# MICROCONTROLLER.net
KiCad netlist of a schematic drawn in Altium Designer
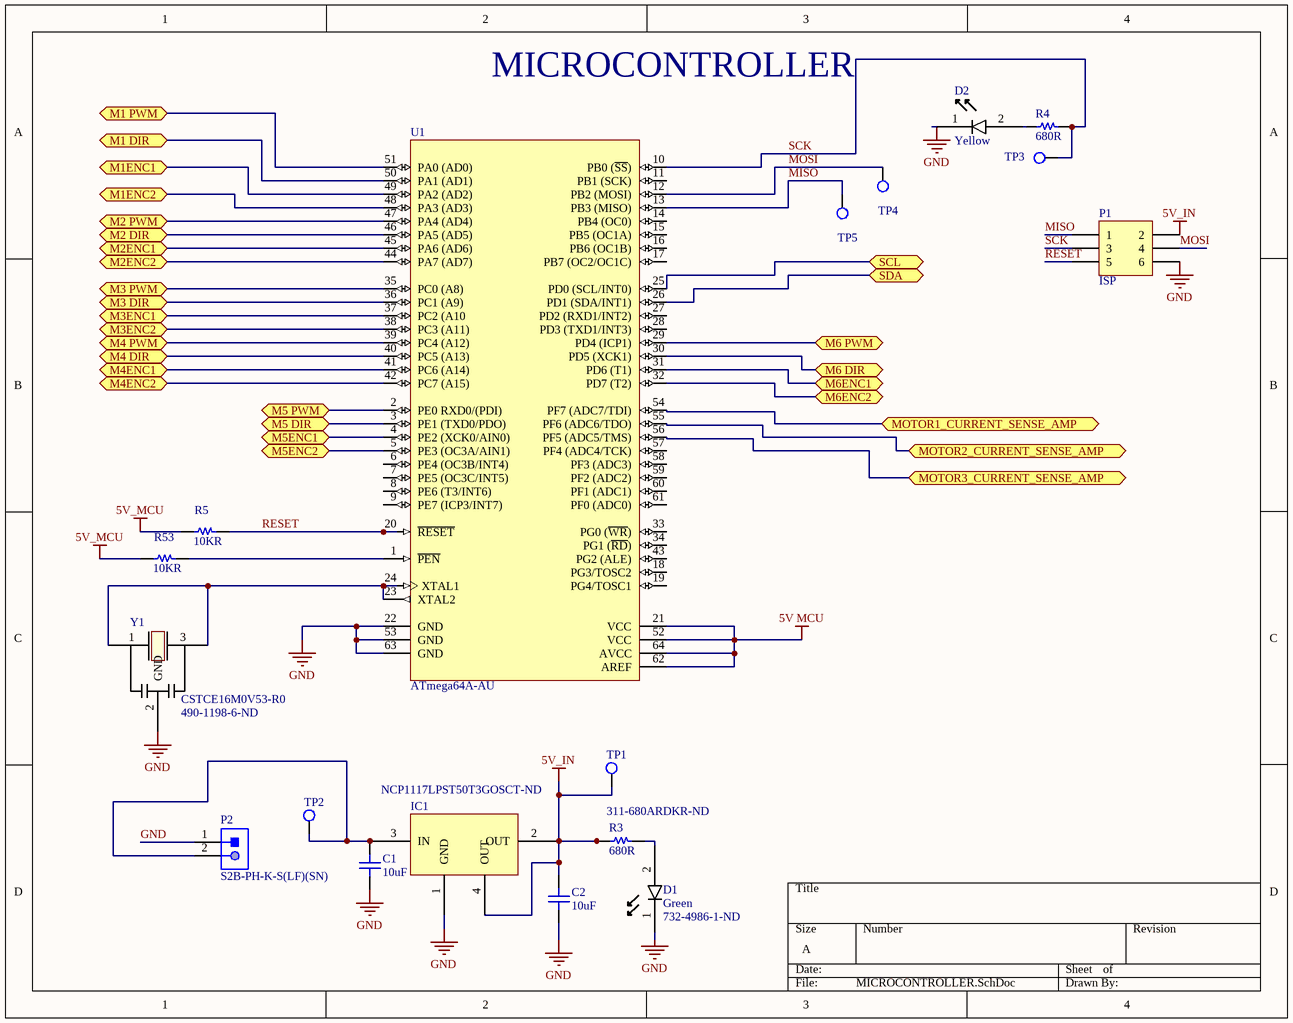
[diagram p0: MICROCONTROLLER.SchDoc]

(export (version "E")
  (design (tool "Eeschema 10.0.6"))
  (components
    (comp (ref "C1")
      (value "10uF")
      (footprint "CAP_ADJ_0805")
      (description "CERAMIC CAPACITOR SMD 0805")
      (fields
        (field (name "MANUFACTURER") "Taiyo Yuden")
        (field (name "MANUFACTURER PART NUMBER") "TMK212BBJ106KG-T")
      )
      (libsource (lib "ORI_MANIPULATOR_BRD") (part "CAP_ADJ_0805"))
    )
    (comp (ref "C2")
      (value "10uF")
      (footprint "CAP_ADJ_0805")
      (description "CERAMIC CAPACITOR SMD 0805")
      (fields
        (field (name "MANUFACTURER") "Taiyo Yuden")
        (field (name "MANUFACTURER PART NUMBER") "TMK212BBJ106KG-T")
      )
      (libsource (lib "ORI_MANIPULATOR_BRD") (part "CAP_ADJ_0805"))
    )
    (comp (ref "D1")
      (value "Green")
      (footprint "LED_150080VS75000")
      (description "LED GREEN CLEAR 0805 SMD")
      (fields
        (field (name "MANUFACTURER") "Wurth Electronics")
        (field (name "MANUFACTURER PART NUMBER") "150080VS75000")
        (field (name "SUPPLIER PART NUMBER 1") "732-4986-1-ND")
      )
      (libsource (lib "ORI_MANIPULATOR_BRD") (part "LED_GRN_150080VS75000"))
    )
    (comp (ref "D2")
      (value "Yellow")
      (footprint "LED_150080VS75000")
      (description "LED YELLOW CLEAR 0805 SMD")
      (fields
        (field (name "MANUFACTURER") "Wurth Electronics")
        (field (name "MANUFACTURER PART NUMBER") "150080YS75000")
      )
      (libsource (lib "ORI_MANIPULATOR_BRD") (part "LED_YLW_150080YS75000"))
    )
    (comp (ref "IC1")
      (value "NCP1117LPST50T3GOSCT-ND")
      (footprint "NCP1117LPST50T3GOSCT-ND")
      (description "IC REG LINEAR 5V 1A SOT223-4")
      (fields
        (field (name "MANUFACTURER") "ON Semiconductor")
        (field (name "MANUFACTURER PART NUMBER") "NCP1117LPST50T3G")
      )
      (libsource (lib "ORI_MANIPULATOR_BRD") (part "NCP1117LPST50T3GOSCT-ND"))
    )
    (comp (ref "P1")
      (value "ISP")
      (footprint "HDR2X3")
      (description "Header, 3-Pin, Dual row")
      (fields (field (name "PUBLISHER") "Altium Limited"))
      (libsource (lib "Miscellaneous Connectors") (part "Header 3X2"))
    )
    (comp (ref "P2")
      (value "S2B-PH-K-S(LF)(SN)")
      (footprint "JST-S2B-PH-K-S_V")
      (fields (field (name "TOLERANCE") "20%"))
      (libsource (lib "Altium Content Vault") (part "CN-1P-M-R2"))
    )
    (comp (ref "R3")
      (value "680R")
      (footprint "RES_ADJ_0805_YAGEO")
      (description "RESISTOR 0805 YAGEO")
      (fields
        (field (name "SUPPLIER PART NUMBER 1") "311-680ARDKR-ND")
        (field (name "MANUFACTURER") "Yageo")
        (field (name "MANUFACTURER PART NUMBER") "RC0805JR-07680RL")
      )
      (libsource (lib "ORI_MANIPULATOR_BRD") (part "RES_ADJ_0805"))
    )
    (comp (ref "R4")
      (value "680R")
      (footprint "RES_ADJ_0805_YAGEO")
      (description "RESISTOR 0805 YAGEO")
      (fields
        (field (name "MANUFACTURER") "Yageo")
        (field (name "MANUFACTURER PART NUMBER") "RC0805JR-07680RL")
      )
      (libsource (lib "ORI_MANIPULATOR_BRD") (part "RES_ADJ_0805"))
    )
    (comp (ref "R5")
      (value "10KR")
      (footprint "RES_ADJ_0805_YAGEO")
      (description "RESISTOR 0805 YAGEO")
      (fields
        (field (name "MANUFACTURER") "Yageo")
        (field (name "MANUFACTURER PART NUMBER") "RC0805JR-0710KL")
      )
      (libsource (lib "ORI_MANIPULATOR_BRD") (part "RES_ADJ_0805"))
    )
    (comp (ref "R53")
      (value "10KR")
      (footprint "RES_ADJ_0805_YAGEO")
      (description "RESISTOR 0805 YAGEO")
      (fields
        (field (name "MANUFACTURER") "Yageo")
        (field (name "MANUFACTURER PART NUMBER") "RC0805JR-0710KL")
      )
      (libsource (lib "ORI_MANIPULATOR_BRD") (part "RES_ADJ_0805"))
    )
    (comp (ref "TP1")
      (value "TEST_POINT")
      (footprint "TEST_POINT")
      (description "TEST POINT PAD")
      (libsource (lib "ORI_MANIPULATOR_BRD") (part "TEST_POINT"))
    )
    (comp (ref "TP2")
      (value "TEST_POINT")
      (footprint "TEST_POINT")
      (description "TEST POINT PAD")
      (libsource (lib "ORI_MANIPULATOR_BRD") (part "TEST_POINT"))
    )
    (comp (ref "TP3")
      (value "TEST_POINT")
      (footprint "TEST_POINT")
      (description "TEST POINT PAD")
      (libsource (lib "ORI_MANIPULATOR_BRD") (part "TEST_POINT"))
    )
    (comp (ref "TP4")
      (value "TEST_POINT")
      (footprint "TEST_POINT")
      (description "TEST POINT PAD")
      (libsource (lib "ORI_MANIPULATOR_BRD") (part "TEST_POINT"))
    )
    (comp (ref "TP5")
      (value "TEST_POINT")
      (footprint "TEST_POINT")
      (description "TEST POINT PAD")
      (libsource (lib "ORI_MANIPULATOR_BRD") (part "TEST_POINT"))
    )
    (comp (ref "U1")
      (value "ATmega64A-AU")
      (footprint "64A_M")
      (libsource (lib "Altium Content Vault") (part "MC-8B-ATM64A-SQ64"))
    )
    (comp (ref "Y1")
      (value "CSTCE16M0V53-R0")
      (footprint "CSTCE16M0V53-R0")
      (description "CER RES 16.0000MHZ 15PF SMD")
      (fields
        (field (name "MANUFACTURER") "Murata")
        (field (name "TOLERANCE") "0.5%")
        (field (name "SUPPLIER PART NUMBER 1") "490-1198-6-ND")
      )
      (libsource (lib "ORI_MANIPULATOR_BRD") (part "CSTCE16M0V53-R0"))
    )
  )
  (nets
    (net (code "1") (name "/M1 DIR") (class "Default")
      (node (ref "U1") (pin "50") (pinfunction "PA1_(AD1)_50") (pintype "bidirectional"))
    )
    (net (code "2") (name "/M1 PWM") (class "Default")
      (node (ref "U1") (pin "51") (pinfunction "PA0_(AD0)_51") (pintype "bidirectional"))
    )
    (net (code "3") (name "/M1ENC1") (class "Default")
      (node (ref "U1") (pin "49") (pinfunction "PA2_(AD2)_49") (pintype "bidirectional"))
    )
    (net (code "4") (name "/M1ENC2") (class "Default")
      (node (ref "U1") (pin "48") (pinfunction "PA3_(AD3)_48") (pintype "bidirectional"))
    )
    (net (code "5") (name "/M2 DIR") (class "Default")
      (node (ref "U1") (pin "46") (pinfunction "PA5_(AD5)_46") (pintype "bidirectional"))
    )
    (net (code "6") (name "/M2 PWM") (class "Default")
      (node (ref "U1") (pin "47") (pinfunction "PA4_(AD4)_47") (pintype "bidirectional"))
    )
    (net (code "7") (name "/M2ENC1") (class "Default")
      (node (ref "U1") (pin "45") (pinfunction "PA6_(AD6)_45") (pintype "bidirectional"))
    )
    (net (code "8") (name "/M2ENC2") (class "Default")
      (node (ref "U1") (pin "44") (pinfunction "PA7_(AD7)_44") (pintype "bidirectional"))
    )
    (net (code "9") (name "/M3 DIR") (class "Default")
      (node (ref "U1") (pin "36") (pinfunction "PC1_(A9)_36") (pintype "bidirectional"))
    )
    (net (code "10") (name "/M3 PWM") (class "Default")
      (node (ref "U1") (pin "35") (pinfunction "PC0_(A8)_35") (pintype "bidirectional"))
    )
    (net (code "11") (name "/M3ENC1") (class "Default")
      (node (ref "U1") (pin "37") (pinfunction "PC2_(A10_37") (pintype "bidirectional"))
    )
    (net (code "12") (name "/M3ENC2") (class "Default")
      (node (ref "U1") (pin "38") (pinfunction "PC3_(A11)_38") (pintype "bidirectional"))
    )
    (net (code "13") (name "/M4 DIR") (class "Default")
      (node (ref "U1") (pin "40") (pinfunction "PC5_(A13)_40") (pintype "bidirectional"))
    )
    (net (code "14") (name "/M4 PWM") (class "Default")
      (node (ref "U1") (pin "39") (pinfunction "PC4_(A12)_39") (pintype "bidirectional"))
    )
    (net (code "15") (name "/M4ENC1") (class "Default")
      (node (ref "U1") (pin "41") (pinfunction "PC6_(A14)_41") (pintype "bidirectional"))
    )
    (net (code "16") (name "/M4ENC2") (class "Default")
      (node (ref "U1") (pin "42") (pinfunction "PC7_(A15)_42") (pintype "bidirectional"))
    )
    (net (code "17") (name "/M5 DIR") (class "Default")
      (node (ref "U1") (pin "3") (pinfunction "PE1_(TXD0/PDO)_3") (pintype "bidirectional"))
    )
    (net (code "18") (name "/M5 PWM") (class "Default")
      (node (ref "U1") (pin "2") (pinfunction "PE0_RXD0/(PDI)_2") (pintype "bidirectional"))
    )
    (net (code "19") (name "/M5ENC1") (class "Default")
      (node (ref "U1") (pin "4") (pinfunction "PE2_(XCK0/AIN0)_4") (pintype "bidirectional"))
    )
    (net (code "20") (name "/M5ENC2") (class "Default")
      (node (ref "U1") (pin "5") (pinfunction "PE3_(OC3A/AIN1)_5") (pintype "bidirectional"))
    )
    (net (code "21") (name "/M6 DIR") (class "Default")
      (node (ref "U1") (pin "30") (pinfunction "PD5_(XCK1)_30") (pintype "bidirectional"))
    )
    (net (code "22") (name "/M6 PWM") (class "Default")
      (node (ref "U1") (pin "29") (pinfunction "PD4_(ICP1)_29") (pintype "bidirectional"))
    )
    (net (code "23") (name "/M6ENC1") (class "Default")
      (node (ref "U1") (pin "31") (pinfunction "PD6_(T1)_31") (pintype "bidirectional"))
    )
    (net (code "24") (name "/M6ENC2") (class "Default")
      (node (ref "U1") (pin "32") (pinfunction "PD7_(T2)_32") (pintype "bidirectional"))
    )
    (net (code "25") (name "/MISO") (class "Default")
      (node (ref "P1") (pin "1") (pinfunction "1_1") (pintype "passive"))
      (node (ref "TP5") (pin "1") (pinfunction "1_1") (pintype "passive"))
      (node (ref "U1") (pin "13") (pinfunction "PB3_(MISO)_13") (pintype "bidirectional"))
    )
    (net (code "26") (name "/MOSI") (class "Default")
      (node (ref "P1") (pin "4") (pinfunction "4_4") (pintype "passive"))
      (node (ref "TP4") (pin "1") (pinfunction "1_1") (pintype "passive"))
      (node (ref "U1") (pin "12") (pinfunction "PB2_(MOSI)_12") (pintype "bidirectional"))
    )
    (net (code "27") (name "/MOTOR1_CURRENT_SENSE_AMP") (class "Default")
      (node (ref "U1") (pin "54") (pinfunction "PF7_(ADC7/TDI)_54") (pintype "bidirectional"))
    )
    (net (code "28") (name "/MOTOR2_CURRENT_SENSE_AMP") (class "Default")
      (node (ref "U1") (pin "55") (pinfunction "PF6_(ADC6/TDO)_55") (pintype "bidirectional"))
    )
    (net (code "29") (name "/MOTOR3_CURRENT_SENSE_AMP") (class "Default")
      (node (ref "U1") (pin "56") (pinfunction "PF5_(ADC5/TMS)_56") (pintype "bidirectional"))
    )
    (net (code "30") (name "/RESET") (class "Default")
      (node (ref "P1") (pin "5") (pinfunction "5_5") (pintype "passive"))
      (node (ref "R5") (pin "2") (pinfunction "2_2") (pintype "passive"))
      (node (ref "U1") (pin "20") (pinfunction "~{RESET}_20") (pintype "input"))
    )
    (net (code "31") (name "/SCK") (class "Default")
      (node (ref "P1") (pin "3") (pinfunction "3_3") (pintype "passive"))
      (node (ref "R4") (pin "2") (pinfunction "2_2") (pintype "passive"))
      (node (ref "TP3") (pin "1") (pinfunction "1_1") (pintype "passive"))
      (node (ref "U1") (pin "10") (pinfunction "PB0_(~{SS})_10") (pintype "bidirectional"))
    )
    (net (code "32") (name "/SCL") (class "Default")
      (node (ref "U1") (pin "25") (pinfunction "PD0_(SCL/INT0)_25") (pintype "bidirectional"))
    )
    (net (code "33") (name "/SDA") (class "Default")
      (node (ref "U1") (pin "26") (pinfunction "PD1_(SDA/INT1)_26") (pintype "bidirectional"))
    )
    (net (code "34") (name "5V MCU") (class "Default")
      (node (ref "U1") (pin "21") (pinfunction "VCC_21") (pintype "power_in"))
      (node (ref "U1") (pin "52") (pinfunction "VCC_52") (pintype "power_in"))
      (node (ref "U1") (pin "62") (pinfunction "AREF_62") (pintype "power_in"))
      (node (ref "U1") (pin "64") (pinfunction "AVCC_64") (pintype "power_in"))
    )
    (net (code "35") (name "5V_IN") (class "Default")
      (node (ref "C2") (pin "2") (pinfunction "2_2") (pintype "passive"))
      (node (ref "IC1") (pin "2") (pinfunction "OUT_2") (pintype "passive"))
      (node (ref "IC1") (pin "4") (pinfunction "OUT_4") (pintype "passive"))
      (node (ref "P1") (pin "2") (pinfunction "2_2") (pintype "passive"))
      (node (ref "R3") (pin "1") (pinfunction "1_1") (pintype "passive"))
      (node (ref "TP1") (pin "1") (pinfunction "1_1") (pintype "passive"))
    )
    (net (code "36") (name "5V_MCU") (class "Default")
      (node (ref "R5") (pin "1") (pinfunction "1_1") (pintype "passive"))
      (node (ref "R53") (pin "1") (pinfunction "1_1") (pintype "passive"))
    )
    (net (code "37") (name "GND") (class "Default")
      (node (ref "C1") (pin "1") (pinfunction "1_1") (pintype "passive"))
      (node (ref "C2") (pin "1") (pinfunction "1_1") (pintype "passive"))
      (node (ref "D1") (pin "1") (pinfunction "1_1") (pintype "passive"))
      (node (ref "D2") (pin "1") (pinfunction "1_1") (pintype "passive"))
      (node (ref "IC1") (pin "1") (pinfunction "GND_1") (pintype "passive"))
      (node (ref "P1") (pin "6") (pinfunction "6_6") (pintype "passive"))
      (node (ref "P2") (pin "1") (pinfunction "1_1") (pintype "passive"))
      (node (ref "U1") (pin "22") (pinfunction "GND_22") (pintype "power_in"))
      (node (ref "U1") (pin "53") (pinfunction "GND_53") (pintype "power_in"))
      (node (ref "U1") (pin "63") (pinfunction "GND_63") (pintype "power_in"))
      (node (ref "Y1") (pin "2") (pinfunction "GND_2") (pintype "passive"))
    )
    (net (code "38") (name "Net-(D1-Pad2)") (class "Default")
      (node (ref "D1") (pin "2") (pinfunction "2_2") (pintype "passive"))
      (node (ref "R3") (pin "2") (pinfunction "2_2") (pintype "passive"))
    )
    (net (code "39") (name "Net-(D2-Pad2)") (class "Default")
      (node (ref "D2") (pin "2") (pinfunction "2_2") (pintype "passive"))
      (node (ref "R4") (pin "1") (pinfunction "1_1") (pintype "passive"))
    )
    (net (code "40") (name "Net-(IC1-IN)") (class "Default")
      (node (ref "C1") (pin "2") (pinfunction "2_2") (pintype "passive"))
      (node (ref "IC1") (pin "3") (pinfunction "IN_3") (pintype "passive"))
      (node (ref "P2") (pin "2") (pinfunction "2_2") (pintype "passive"))
      (node (ref "TP2") (pin "1") (pinfunction "1_1") (pintype "passive"))
    )
    (net (code "41") (name "Net-(U1-XTAL1)") (class "Default")
      (node (ref "U1") (pin "23") (pinfunction "XTAL2_23") (pintype "output"))
      (node (ref "U1") (pin "24") (pinfunction "XTAL1_24") (pintype "input"))
      (node (ref "Y1") (pin "1") (pinfunction "1_1") (pintype "passive"))
      (node (ref "Y1") (pin "3") (pinfunction "3_3") (pintype "passive"))
    )
    (net (code "42") (name "Net-(U1-~{PEN})") (class "Default")
      (node (ref "R53") (pin "2") (pinfunction "2_2") (pintype "passive"))
      (node (ref "U1") (pin "1") (pinfunction "~{PEN}_1") (pintype "input"))
    )
    (net (code "43") (name "unconnected-(U1-PB1_(SCK)-Pad11)") (class "Default")
      (node (ref "U1") (pin "11") (pinfunction "PB1_(SCK)_11") (pintype "bidirectional"))
    )
    (net (code "44") (name "unconnected-(U1-PB4_(OC0)-Pad14)") (class "Default")
      (node (ref "U1") (pin "14") (pinfunction "PB4_(OC0)_14") (pintype "bidirectional"))
    )
    (net (code "45") (name "unconnected-(U1-PB5_(OC1A)-Pad15)") (class "Default")
      (node (ref "U1") (pin "15") (pinfunction "PB5_(OC1A)_15") (pintype "bidirectional"))
    )
    (net (code "46") (name "unconnected-(U1-PB6_(OC1B)-Pad16)") (class "Default")
      (node (ref "U1") (pin "16") (pinfunction "PB6_(OC1B)_16") (pintype "bidirectional"))
    )
    (net (code "47") (name "unconnected-(U1-PB7_(OC2{slash}OC1C)-Pad17)") (class "Default")
      (node (ref "U1") (pin "17") (pinfunction "PB7_(OC2/OC1C)_17") (pintype "bidirectional"))
    )
    (net (code "48") (name "unconnected-(U1-PD2_(RXD1{slash}INT2)-Pad27)") (class "Default")
      (node (ref "U1") (pin "27") (pinfunction "PD2_(RXD1/INT2)_27") (pintype "bidirectional"))
    )
    (net (code "49") (name "unconnected-(U1-PD3_(TXD1{slash}INT3)-Pad28)") (class "Default")
      (node (ref "U1") (pin "28") (pinfunction "PD3_(TXD1/INT3)_28") (pintype "bidirectional"))
    )
    (net (code "50") (name "unconnected-(U1-PE4_(OC3B{slash}INT4)-Pad6)") (class "Default")
      (node (ref "U1") (pin "6") (pinfunction "PE4_(OC3B/INT4)_6") (pintype "bidirectional"))
    )
    (net (code "51") (name "unconnected-(U1-PE5_(OC3C{slash}INT5)-Pad7)") (class "Default")
      (node (ref "U1") (pin "7") (pinfunction "PE5_(OC3C/INT5)_7") (pintype "bidirectional"))
    )
    (net (code "52") (name "unconnected-(U1-PE6_(T3{slash}INT6)-Pad8)") (class "Default")
      (node (ref "U1") (pin "8") (pinfunction "PE6_(T3/INT6)_8") (pintype "bidirectional"))
    )
    (net (code "53") (name "unconnected-(U1-PE7_(ICP3{slash}INT7)-Pad9)") (class "Default")
      (node (ref "U1") (pin "9") (pinfunction "PE7_(ICP3/INT7)_9") (pintype "bidirectional"))
    )
    (net (code "54") (name "unconnected-(U1-PF0_(ADC0)-Pad61)") (class "Default")
      (node (ref "U1") (pin "61") (pinfunction "PF0_(ADC0)_61") (pintype "bidirectional"))
    )
    (net (code "55") (name "unconnected-(U1-PF1_(ADC1)-Pad60)") (class "Default")
      (node (ref "U1") (pin "60") (pinfunction "PF1_(ADC1)_60") (pintype "bidirectional"))
    )
    (net (code "56") (name "unconnected-(U1-PF2_(ADC2)-Pad59)") (class "Default")
      (node (ref "U1") (pin "59") (pinfunction "PF2_(ADC2)_59") (pintype "bidirectional"))
    )
    (net (code "57") (name "unconnected-(U1-PF3_(ADC3)-Pad58)") (class "Default")
      (node (ref "U1") (pin "58") (pinfunction "PF3_(ADC3)_58") (pintype "bidirectional"))
    )
    (net (code "58") (name "unconnected-(U1-PF4_(ADC4{slash}TCK)-Pad57)") (class "Default")
      (node (ref "U1") (pin "57") (pinfunction "PF4_(ADC4/TCK)_57") (pintype "bidirectional"))
    )
    (net (code "59") (name "unconnected-(U1-PG0_(~{WR})-Pad33)") (class "Default")
      (node (ref "U1") (pin "33") (pinfunction "PG0_(~{WR})_33") (pintype "bidirectional"))
    )
    (net (code "60") (name "unconnected-(U1-PG1_(~{RD})-Pad34)") (class "Default")
      (node (ref "U1") (pin "34") (pinfunction "PG1_(~{RD})_34") (pintype "bidirectional"))
    )
    (net (code "61") (name "unconnected-(U1-PG2_(ALE)-Pad43)") (class "Default")
      (node (ref "U1") (pin "43") (pinfunction "PG2_(ALE)_43") (pintype "bidirectional"))
    )
    (net (code "62") (name "unconnected-(U1-PG3{slash}TOSC2-Pad18)") (class "Default")
      (node (ref "U1") (pin "18") (pinfunction "PG3/TOSC2_18") (pintype "bidirectional"))
    )
    (net (code "63") (name "unconnected-(U1-PG4{slash}TOSC1-Pad19)") (class "Default")
      (node (ref "U1") (pin "19") (pinfunction "PG4/TOSC1_19") (pintype "bidirectional"))
    )
  )
)
